# 780-00055_rev2_Pg5_SCH_NRES_Temp_Meas_8-.net
KiCad netlist of a schematic drawn in Altium Designer
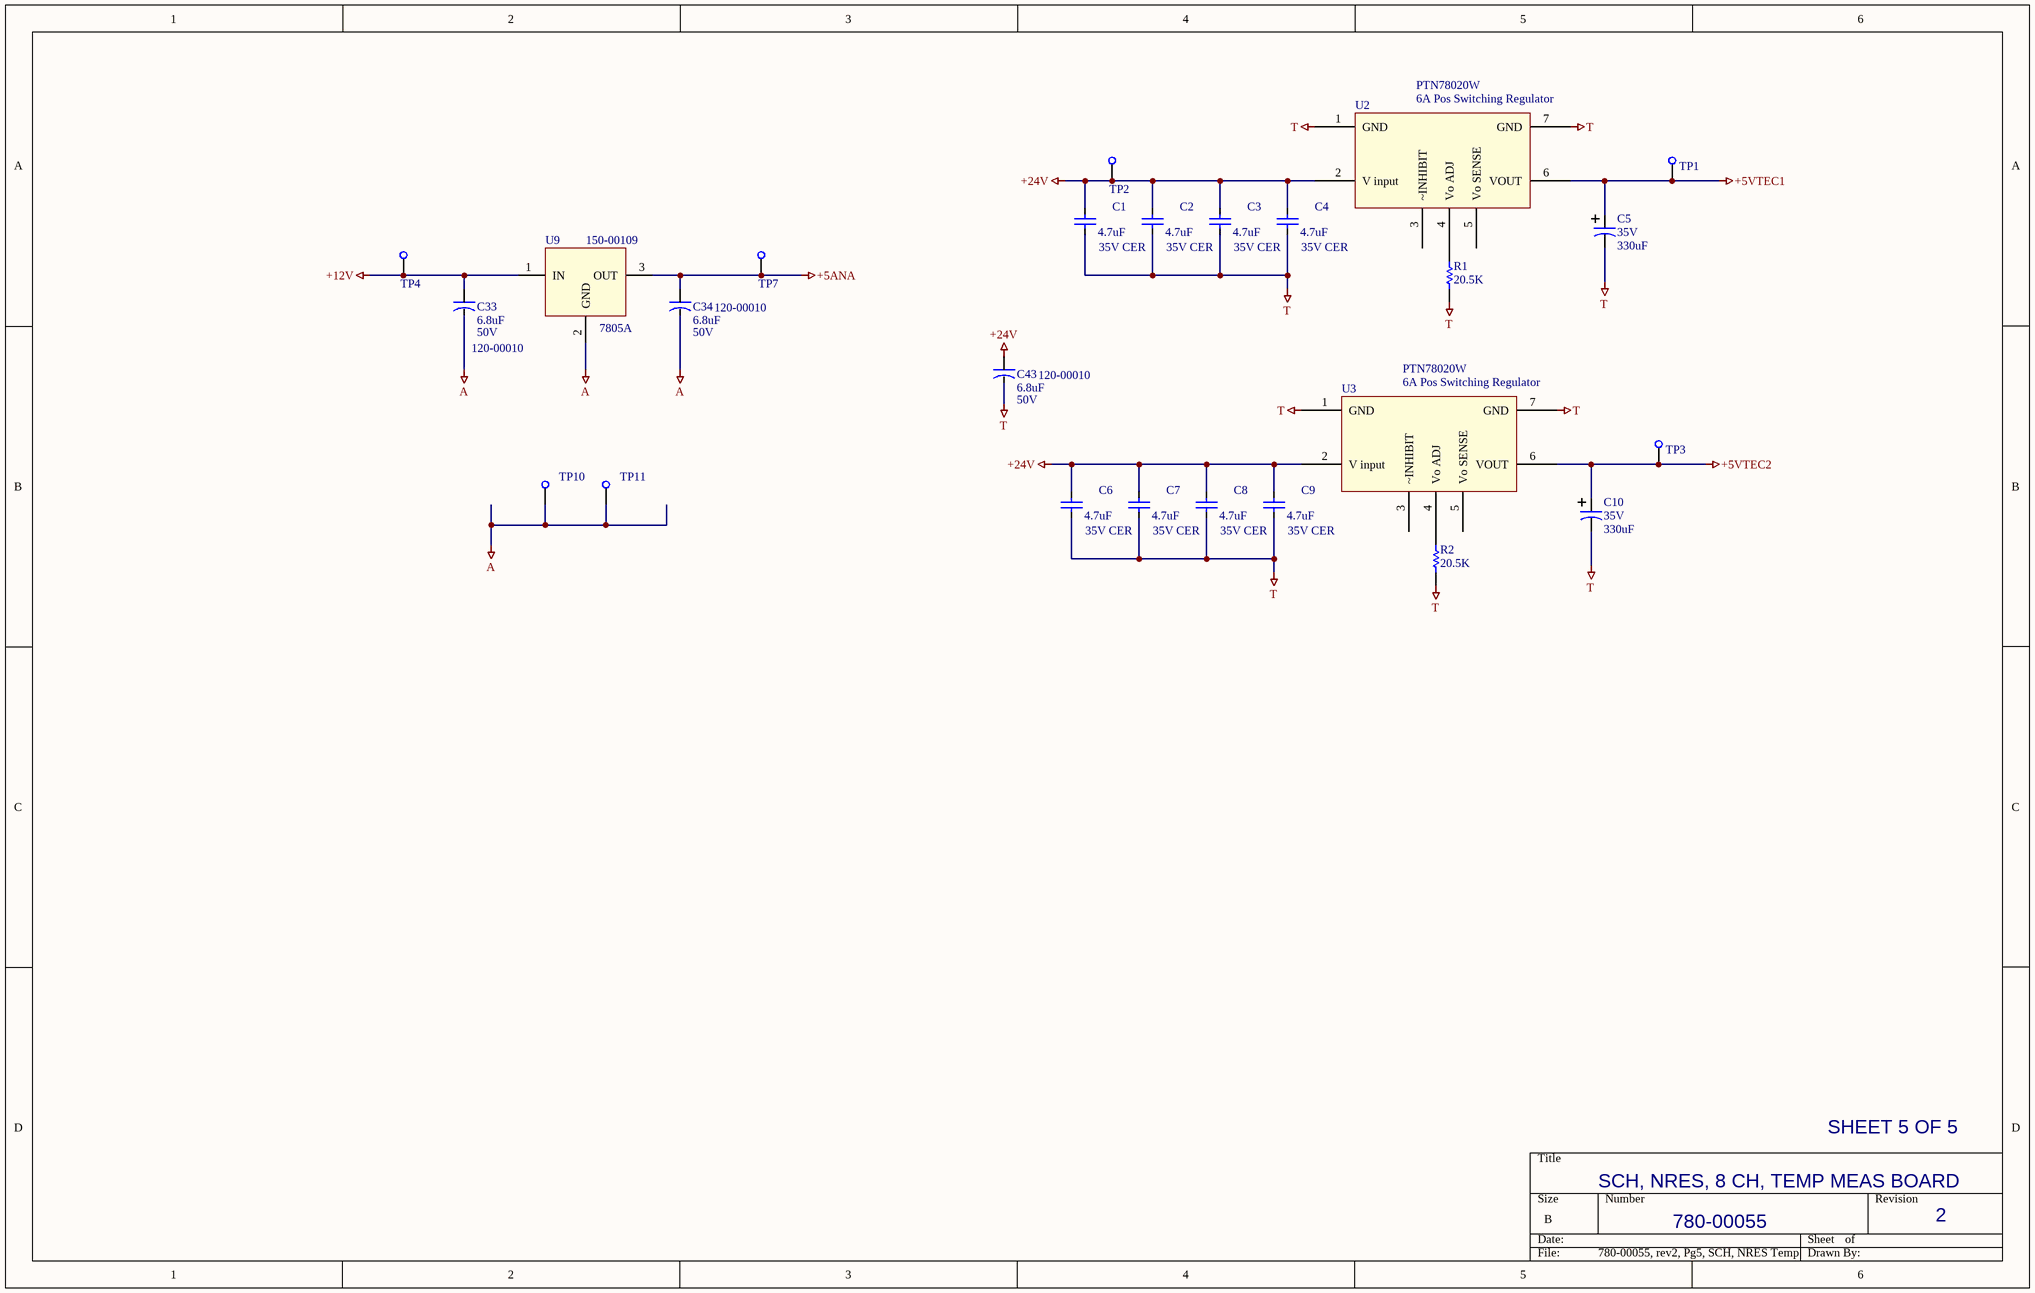
[diagram p0: 780-00055, rev2, Pg5, SCH, NRES Temp Meas, 8-Chan RTD .SchDoc]

(export (version "E")
  (design (tool "Eeschema 10.0.6"))
  (components
    (comp (ref "C1")
      (value "35V CER")
      (footprint "SMD_0805")
      (description "Capacitor")
      (fields (field (name "ALTIUM_VALUE") "4.7uF"))
      (libsource (lib "Richs Schematic Components") (part "Cap SMD"))
    )
    (comp (ref "C2")
      (value "35V CER")
      (footprint "SMD_0805")
      (description "Capacitor")
      (fields (field (name "ALTIUM_VALUE") "4.7uF"))
      (libsource (lib "Richs Schematic Components") (part "Cap SMD"))
    )
    (comp (ref "C3")
      (value "35V CER")
      (footprint "SMD_0805")
      (description "Capacitor")
      (fields (field (name "ALTIUM_VALUE") "4.7uF"))
      (libsource (lib "Richs Schematic Components") (part "Cap SMD"))
    )
    (comp (ref "C4")
      (value "35V CER")
      (footprint "SMD_0805")
      (description "Capacitor")
      (fields (field (name "ALTIUM_VALUE") "4.7uF"))
      (libsource (lib "Richs Schematic Components") (part "Cap SMD"))
    )
    (comp (ref "C5")
      (value "35V")
      (footprint "CAP, Thru Hole 10mm dia")
      (description "Radial Thru hole")
      (fields (field (name "ALTIUM_VALUE") "330uF"))
      (libsource (lib "Richs Schematic Components") (part "Cap Elec, 330 uF, 35V"))
    )
    (comp (ref "C6")
      (value "35V CER")
      (footprint "SMD_0805")
      (description "Capacitor")
      (fields (field (name "ALTIUM_VALUE") "4.7uF"))
      (libsource (lib "Richs Schematic Components") (part "Cap SMD"))
    )
    (comp (ref "C7")
      (value "35V CER")
      (footprint "SMD_0805")
      (description "Capacitor")
      (fields (field (name "ALTIUM_VALUE") "4.7uF"))
      (libsource (lib "Richs Schematic Components") (part "Cap SMD"))
    )
    (comp (ref "C8")
      (value "35V CER")
      (footprint "SMD_0805")
      (description "Capacitor")
      (fields (field (name "ALTIUM_VALUE") "4.7uF"))
      (libsource (lib "Richs Schematic Components") (part "Cap SMD"))
    )
    (comp (ref "C9")
      (value "35V CER")
      (footprint "SMD_0805")
      (description "Capacitor")
      (fields (field (name "ALTIUM_VALUE") "4.7uF"))
      (libsource (lib "Richs Schematic Components") (part "Cap SMD"))
    )
    (comp (ref "C10")
      (value "35V")
      (footprint "CAP, Thru Hole 10mm dia")
      (description "Radial Thru hole")
      (fields (field (name "ALTIUM_VALUE") "330uF"))
      (libsource (lib "Richs Schematic Components") (part "Cap Elec, 330 uF, 35V"))
    )
    (comp (ref "C33")
      (value "50V")
      (footprint "SMD_CAP_6032")
      (description "outline 6.0mm x 3.2mm")
      (fields
        (field (name "ALTIUM_VALUE") "6.8uF")
        (field (name "MANUFACTURER") "AVX")
        (field (name "LCO P/N") "120-00010")
      )
      (libsource (lib "Richs Schematic Components") (part "Cap Tant 35V"))
    )
    (comp (ref "C34")
      (value "50V")
      (footprint "SMD_CAP_6032")
      (description "outline 6.0mm x 3.2mm")
      (fields
        (field (name "ALTIUM_VALUE") "6.8uF")
        (field (name "MANUFACTURER") "AVX")
        (field (name "LCO P/N") "120-00010")
      )
      (libsource (lib "Richs Schematic Components") (part "Cap Tant 35V"))
    )
    (comp (ref "C43")
      (value "50V")
      (footprint "SMD_CAP_6032")
      (description "outline 6.0mm x 3.2mm")
      (fields
        (field (name "ALTIUM_VALUE") "6.8uF")
        (field (name "MANUFACTURER") "AVX")
        (field (name "LCO P/N") "120-00010")
      )
      (libsource (lib "Richs Schematic Components") (part "Cap Tant 35V"))
    )
    (comp (ref "R1")
      (value "20.5K")
      (footprint "SMD_0805")
      (description "Resistor 0805")
      (fields (field (name "MANUFACTURER") "Vishay/Dale") (field (name "Comment") "Res 0805"))
      (libsource (lib "Richs Schematic Components") (part "Res SMD"))
    )
    (comp (ref "R2")
      (value "20.5K")
      (footprint "SMD_0805")
      (description "Resistor 0805")
      (fields (field (name "MANUFACTURER") "Vishay/Dale") (field (name "Comment") "Res 0805"))
      (libsource (lib "Richs Schematic Components") (part "Res SMD"))
    )
    (comp (ref "TP1")
      (value "Test point")
      (footprint "Protel 99SE BANKS PCB:PAD_80D_052H")
      (description "Test Point")
      (fields (field (name "MANUFACTURER") "Keystone"))
      (libsource (lib "Richs Schematic Components") (part "Test point"))
    )
    (comp (ref "TP2")
      (value "Test point")
      (footprint "Protel 99SE BANKS PCB:PAD_80D_052H")
      (description "Test Point")
      (fields (field (name "MANUFACTURER") "Keystone"))
      (libsource (lib "Richs Schematic Components") (part "Test point"))
    )
    (comp (ref "TP3")
      (value "Test point")
      (footprint "Protel 99SE BANKS PCB:PAD_80D_052H")
      (description "Test Point")
      (fields (field (name "MANUFACTURER") "Keystone"))
      (libsource (lib "Richs Schematic Components") (part "Test point"))
    )
    (comp (ref "TP4")
      (value "Test point")
      (footprint "Protel 99SE BANKS PCB:PAD_80D_052H")
      (description "Test Point")
      (fields (field (name "MANUFACTURER") "Keystone"))
      (libsource (lib "Richs Schematic Components") (part "Test point"))
    )
    (comp (ref "TP7")
      (value "Test point")
      (footprint "Protel 99SE BANKS PCB:PAD_80D_052H")
      (description "Test Point")
      (fields (field (name "MANUFACTURER") "Keystone"))
      (libsource (lib "Richs Schematic Components") (part "Test point"))
    )
    (comp (ref "TP10")
      (value "Test point")
      (footprint "Protel 99SE BANKS PCB:PAD_80D_052H")
      (description "Test Point")
      (fields (field (name "MANUFACTURER") "Keystone"))
      (libsource (lib "Richs Schematic Components") (part "Test point"))
    )
    (comp (ref "TP11")
      (value "Test point")
      (footprint "Protel 99SE BANKS PCB:PAD_80D_052H")
      (description "Test Point")
      (fields (field (name "MANUFACTURER") "Keystone"))
      (libsource (lib "Richs Schematic Components") (part "Test point"))
    )
    (comp (ref "U2")
      (value "6A Pos Switching Regulator")
      (footprint "TEXAS Inst Switching Regulator")
      (description "Pos Adj Switching Regulator")
      (fields (field (name "ALTIUM_VALUE") "PTN78020W"))
      (libsource (lib "Richs Schematic Components") (part "PTN78020W"))
    )
    (comp (ref "U3")
      (value "6A Pos Switching Regulator")
      (footprint "TEXAS Inst Switching Regulator")
      (description "Pos Adj Switching Regulator")
      (fields (field (name "ALTIUM_VALUE") "PTN78020W"))
      (libsource (lib "Richs Schematic Components") (part "PTN78020W"))
    )
    (comp (ref "U9")
      (value "7805A")
      (footprint "TO-220 w/Heatsink 7136DG")
      (fields
        (field (name "LCO P/N") "150-00109")
        (field (name "MANUFACTURER") "On Semi")
        (field (name "Comment") "Voltage Reg, Pos Fixed")
      )
      (libsource (lib "Richs Schematic Components") (part "Voltage Reg, Pos Fixed"))
    )
  )
  (nets
    (net (code "1") (name "+5ANA") (class "Default")
      (node (ref "C34") (pin "pos") (pinfunction "1_pos") (pintype "passive"))
      (node (ref "TP7") (pin "1") (pinfunction "TP_1") (pintype "passive"))
      (node (ref "U9") (pin "3") (pinfunction "OUT_3") (pintype "passive"))
    )
    (net (code "2") (name "+5VTEC1") (class "Default")
      (node (ref "C5") (pin "1") (pinfunction "1_1") (pintype "passive"))
      (node (ref "TP1") (pin "1") (pinfunction "TP_1") (pintype "passive"))
      (node (ref "U2") (pin "6") (pinfunction "VOUT_6") (pintype "passive"))
    )
    (net (code "3") (name "+5VTEC2") (class "Default")
      (node (ref "C10") (pin "1") (pinfunction "1_1") (pintype "passive"))
      (node (ref "TP3") (pin "1") (pinfunction "TP_1") (pintype "passive"))
      (node (ref "U3") (pin "6") (pinfunction "VOUT_6") (pintype "passive"))
    )
    (net (code "4") (name "+12V") (class "Default")
      (node (ref "C33") (pin "pos") (pinfunction "1_pos") (pintype "passive"))
      (node (ref "TP4") (pin "1") (pinfunction "TP_1") (pintype "passive"))
      (node (ref "U9") (pin "1") (pinfunction "IN_1") (pintype "passive"))
    )
    (net (code "5") (name "+24V") (class "Default")
      (node (ref "C1") (pin "2") (pinfunction "2_2") (pintype "passive"))
      (node (ref "C2") (pin "2") (pinfunction "2_2") (pintype "passive"))
      (node (ref "C3") (pin "2") (pinfunction "2_2") (pintype "passive"))
      (node (ref "C4") (pin "2") (pinfunction "2_2") (pintype "passive"))
      (node (ref "C43") (pin "pos") (pinfunction "1_pos") (pintype "passive"))
      (node (ref "C6") (pin "2") (pinfunction "2_2") (pintype "passive"))
      (node (ref "C7") (pin "2") (pinfunction "2_2") (pintype "passive"))
      (node (ref "C8") (pin "2") (pinfunction "2_2") (pintype "passive"))
      (node (ref "C9") (pin "2") (pinfunction "2_2") (pintype "passive"))
      (node (ref "TP2") (pin "1") (pinfunction "TP_1") (pintype "passive"))
      (node (ref "U2") (pin "2") (pinfunction "V_input_2") (pintype "passive"))
      (node (ref "U3") (pin "2") (pinfunction "V_input_2") (pintype "passive"))
    )
    (net (code "6") (name "A") (class "Default")
      (node (ref "C33") (pin "neg") (pinfunction "2_neg") (pintype "passive"))
      (node (ref "C34") (pin "neg") (pinfunction "2_neg") (pintype "passive"))
      (node (ref "TP10") (pin "1") (pinfunction "TP_1") (pintype "passive"))
      (node (ref "TP11") (pin "1") (pinfunction "TP_1") (pintype "passive"))
      (node (ref "U9") (pin "2") (pinfunction "GND_2") (pintype "passive"))
    )
    (net (code "7") (name "Net-(U2-Vo_ADJ)") (class "Default")
      (node (ref "R1") (pin "2") (pinfunction "2_2") (pintype "passive"))
      (node (ref "U2") (pin "4") (pinfunction "Vo_ADJ_4") (pintype "passive"))
    )
    (net (code "8") (name "Net-(U3-Vo_ADJ)") (class "Default")
      (node (ref "R2") (pin "2") (pinfunction "2_2") (pintype "passive"))
      (node (ref "U3") (pin "4") (pinfunction "Vo_ADJ_4") (pintype "passive"))
    )
    (net (code "9") (name "T") (class "Default")
      (node (ref "C1") (pin "1") (pinfunction "1_1") (pintype "passive"))
      (node (ref "C10") (pin "2") (pinfunction "2_2") (pintype "passive"))
      (node (ref "C2") (pin "1") (pinfunction "1_1") (pintype "passive"))
      (node (ref "C3") (pin "1") (pinfunction "1_1") (pintype "passive"))
      (node (ref "C4") (pin "1") (pinfunction "1_1") (pintype "passive"))
      (node (ref "C43") (pin "neg") (pinfunction "2_neg") (pintype "passive"))
      (node (ref "C5") (pin "2") (pinfunction "2_2") (pintype "passive"))
      (node (ref "C6") (pin "1") (pinfunction "1_1") (pintype "passive"))
      (node (ref "C7") (pin "1") (pinfunction "1_1") (pintype "passive"))
      (node (ref "C8") (pin "1") (pinfunction "1_1") (pintype "passive"))
      (node (ref "C9") (pin "1") (pinfunction "1_1") (pintype "passive"))
      (node (ref "R1") (pin "1") (pinfunction "1_1") (pintype "passive"))
      (node (ref "R2") (pin "1") (pinfunction "1_1") (pintype "passive"))
      (node (ref "U2") (pin "1") (pinfunction "GND_1") (pintype "passive"))
      (node (ref "U2") (pin "7") (pinfunction "GND_7") (pintype "passive"))
      (node (ref "U3") (pin "1") (pinfunction "GND_1") (pintype "passive"))
      (node (ref "U3") (pin "7") (pinfunction "GND_7") (pintype "passive"))
    )
    (net (code "10") (name "unconnected-(U2-Vo_SENSE-Pad5)") (class "Default")
      (node (ref "U2") (pin "5") (pinfunction "Vo_SENSE_5") (pintype "passive"))
    )
    (net (code "11") (name "unconnected-(U2-~INHIBIT-Pad3)") (class "Default")
      (node (ref "U2") (pin "3") (pinfunction "~INHIBIT_3") (pintype "passive"))
    )
    (net (code "12") (name "unconnected-(U3-Vo_SENSE-Pad5)") (class "Default")
      (node (ref "U3") (pin "5") (pinfunction "Vo_SENSE_5") (pintype "passive"))
    )
    (net (code "13") (name "unconnected-(U3-~INHIBIT-Pad3)") (class "Default")
      (node (ref "U3") (pin "3") (pinfunction "~INHIBIT_3") (pintype "passive"))
    )
  )
)
